# rgb.net
KiCad netlist of a schematic drawn in EAGLE
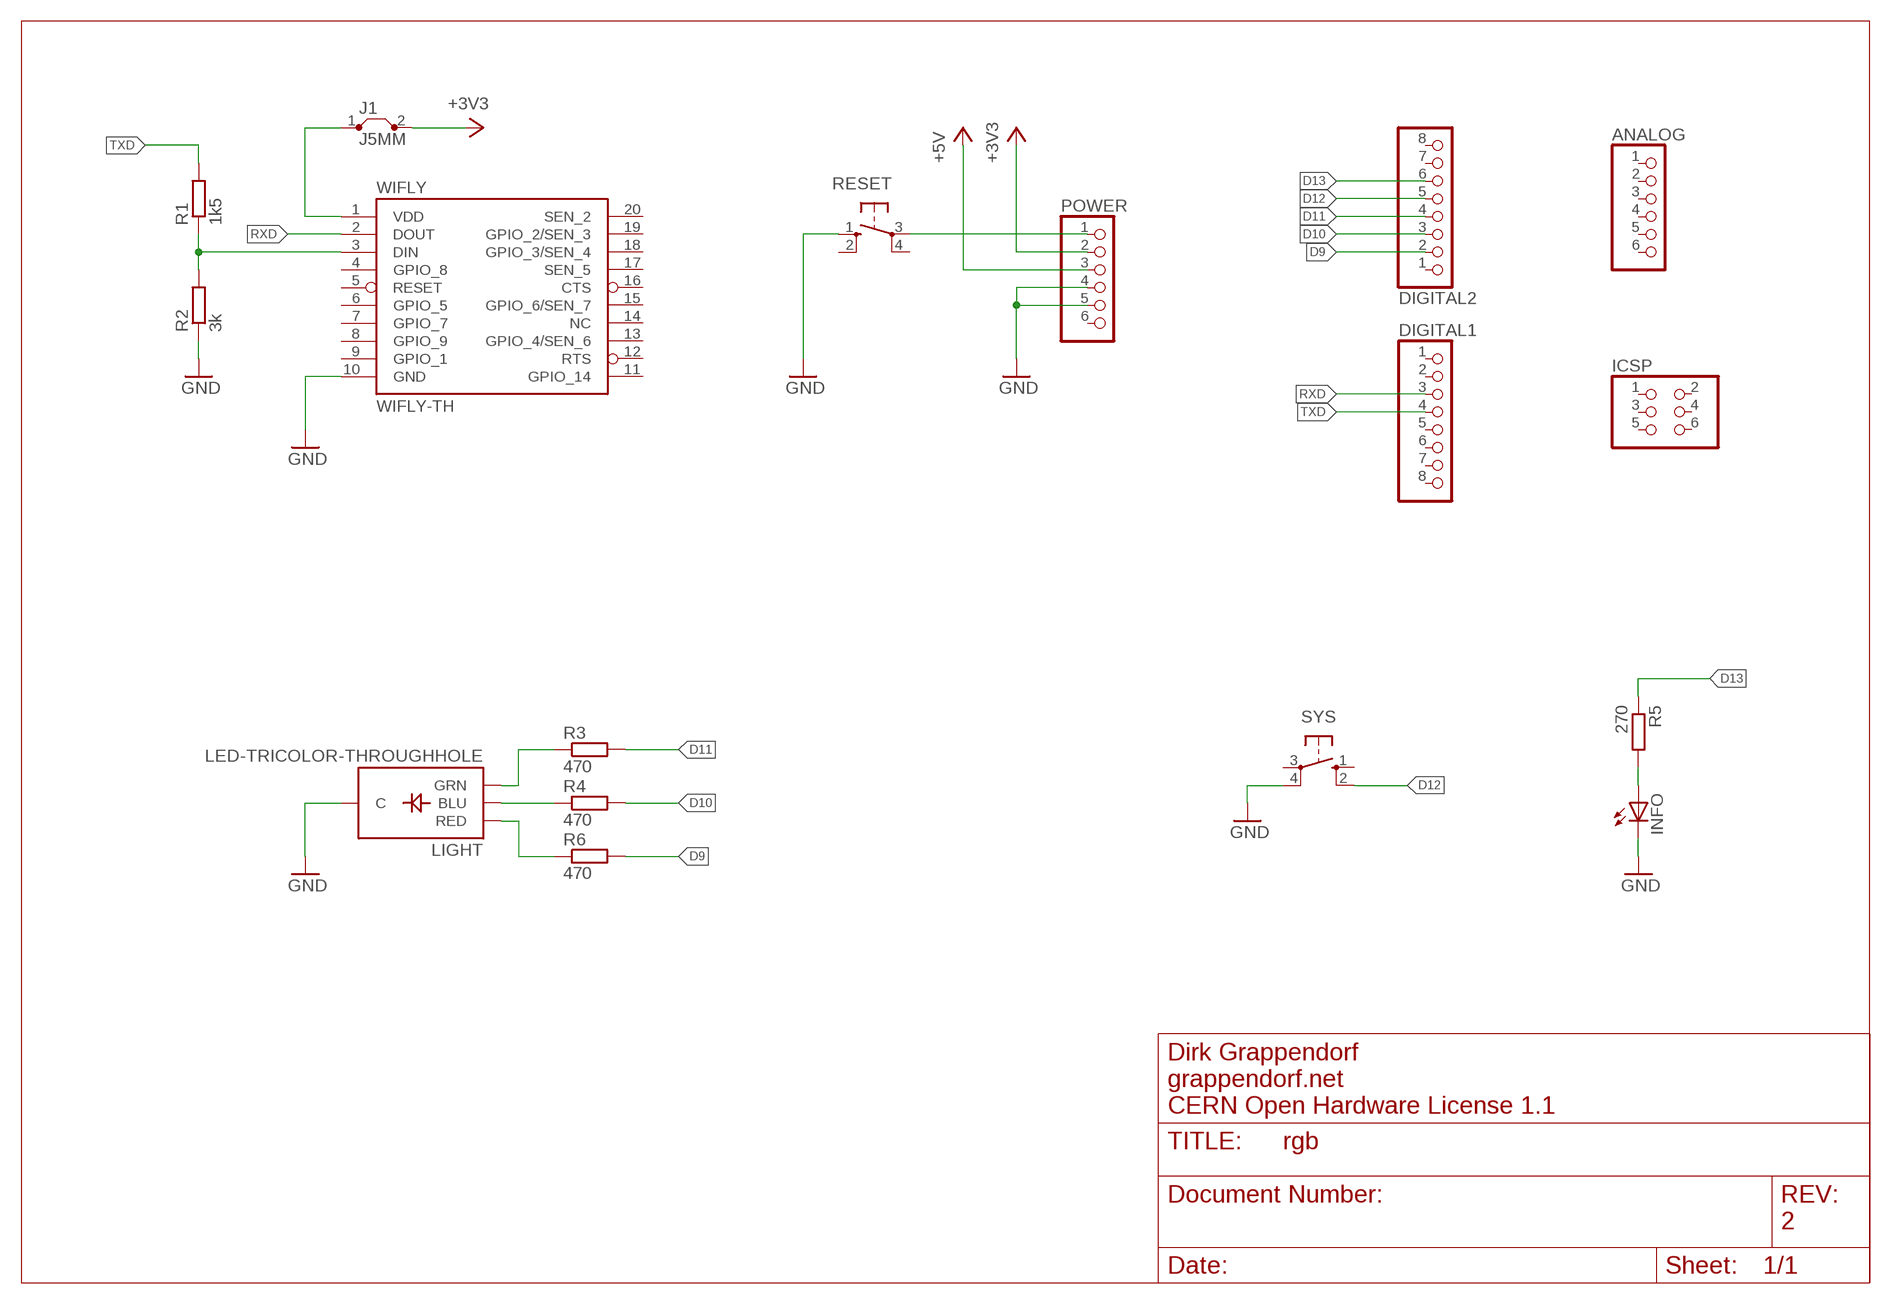
[diagram p0: schematic, sheet 1]

(export (version "E")
  (design (tool "Eeschema 10.0.6"))
  (components
    (comp (ref "ANALOG")
      (value "PINHD-1X6")
      (footprint "eagle-import:1X06")
      (libsource (lib "eagle-import") (part "PINHD-1X6"))
    )
    (comp (ref "DIGITAL1")
      (value "PINHD-1X8TH")
      (footprint "eagle-import:1X08-TH")
      (libsource (lib "eagle-import") (part "PINHD-1X8TH"))
    )
    (comp (ref "DIGITAL2")
      (value "PINHD-1X8_2.54")
      (footprint "eagle-import:1X08")
      (libsource (lib "eagle-import") (part "PINHD-1X8_2.54"))
    )
    (comp (ref "ICSP")
      (value "PINHD-2X3")
      (footprint "eagle-import:2X03")
      (libsource (lib "eagle-import") (part "PINHD-2X3"))
    )
    (comp (ref "INFO")
      (value "LED3MM")
      (footprint "eagle-import:LED3MM")
      (libsource (lib "eagle-import") (part "LED3MM"))
    )
    (comp (ref "J1")
      (value "J5MM")
      (footprint "eagle-import:05")
      (libsource (lib "eagle-import") (part "J5MM"))
    )
    (comp (ref "LIGHT")
      (value "LED-TRICOLOR-THROUGHHOLE")
      (footprint "eagle-import:LED-TRICOLOR-THROUGHHOLE")
      (libsource (lib "eagle-import") (part "LED-TRICOLOR-THROUGHHOLE"))
    )
    (comp (ref "POWER")
      (value "PINHD-1X6_2.54")
      (footprint "eagle-import:1X06")
      (libsource (lib "eagle-import") (part "PINHD-1X6_2.54"))
    )
    (comp (ref "R1")
      (value "1k5")
      (footprint "eagle-import:0204_7")
      (libsource (lib "eagle-import") (part "R-EU_0204/7"))
    )
    (comp (ref "R2")
      (value "3k")
      (footprint "eagle-import:0204_7")
      (libsource (lib "eagle-import") (part "R-EU_0204/7"))
    )
    (comp (ref "R3")
      (value "470")
      (footprint "eagle-import:0204_7")
      (libsource (lib "eagle-import") (part "R-EU_0204/7"))
    )
    (comp (ref "R4")
      (value "470")
      (footprint "eagle-import:0204_7")
      (libsource (lib "eagle-import") (part "R-EU_0204/7"))
    )
    (comp (ref "R5")
      (value "270")
      (footprint "eagle-import:0204_7")
      (libsource (lib "eagle-import") (part "R-EU_0204/7"))
    )
    (comp (ref "R6")
      (value "470")
      (footprint "eagle-import:0204_7")
      (libsource (lib "eagle-import") (part "R-EU_0204/7"))
    )
    (comp (ref "RESET")
      (value "10-XX")
      (footprint "eagle-import:B3F-10XX")
      (libsource (lib "eagle-import") (part "10-XX"))
    )
    (comp (ref "SYS")
      (value "10-XX")
      (footprint "eagle-import:B3F-10XX")
      (libsource (lib "eagle-import") (part "10-XX"))
    )
    (comp (ref "WIFLY")
      (value "WIFLY-TH")
      (footprint "eagle-import:WIFLY-TH")
      (libsource (lib "eagle-import") (part "WIFLY-TH"))
    )
  )
  (nets
    (net (code "1") (name "+3V3") (class "Default")
      (node (ref "J1") (pin "2") (pinfunction "2_2") (pintype "passive"))
      (node (ref "POWER") (pin "2") (pinfunction "2_2") (pintype "passive"))
    )
    (net (code "2") (name "+5V") (class "Default")
      (node (ref "POWER") (pin "3") (pinfunction "3_3") (pintype "passive"))
    )
    (net (code "3") (name "D9") (class "Default")
      (node (ref "DIGITAL2") (pin "2") (pinfunction "2_2") (pintype "passive"))
      (node (ref "R6") (pin "2") (pinfunction "2_2") (pintype "passive"))
    )
    (net (code "4") (name "D10") (class "Default")
      (node (ref "DIGITAL2") (pin "3") (pinfunction "3_3") (pintype "passive"))
      (node (ref "R4") (pin "2") (pinfunction "2_2") (pintype "passive"))
    )
    (net (code "5") (name "D11") (class "Default")
      (node (ref "DIGITAL2") (pin "4") (pinfunction "4_4") (pintype "passive"))
      (node (ref "R3") (pin "2") (pinfunction "2_2") (pintype "passive"))
    )
    (net (code "6") (name "D12") (class "Default")
      (node (ref "DIGITAL2") (pin "5") (pinfunction "5_5") (pintype "passive"))
      (node (ref "SYS") (pin "2") (pinfunction "S1_2") (pintype "passive"))
    )
    (net (code "7") (name "D13") (class "Default")
      (node (ref "DIGITAL2") (pin "6") (pinfunction "6_6") (pintype "passive"))
      (node (ref "R5") (pin "1") (pinfunction "1_1") (pintype "passive"))
    )
    (net (code "8") (name "GND") (class "Default")
      (node (ref "INFO") (pin "K") (pinfunction "C_K") (pintype "passive"))
      (node (ref "LIGHT") (pin "GND") (pinfunction "C_GND") (pintype "bidirectional"))
      (node (ref "POWER") (pin "4") (pinfunction "4_4") (pintype "passive"))
      (node (ref "POWER") (pin "5") (pinfunction "5_5") (pintype "passive"))
      (node (ref "R2") (pin "1") (pinfunction "1_1") (pintype "passive"))
      (node (ref "RESET") (pin "1") (pinfunction "S_1") (pintype "passive"))
      (node (ref "SYS") (pin "4") (pinfunction "P1_4") (pintype "passive"))
      (node (ref "WIFLY") (pin "10") (pinfunction "GND_10") (pintype "power_in"))
    )
    (net (code "9") (name "Net-(INFO-PadA)") (class "Default")
      (node (ref "INFO") (pin "A") (pinfunction "A_A") (pintype "passive"))
      (node (ref "R5") (pin "2") (pinfunction "2_2") (pintype "passive"))
    )
    (net (code "10") (name "Net-(LIGHT-PadBLU)") (class "Default")
      (node (ref "LIGHT") (pin "BLU") (pinfunction "BLU_BLU") (pintype "bidirectional"))
      (node (ref "R4") (pin "1") (pinfunction "1_1") (pintype "passive"))
    )
    (net (code "11") (name "Net-(LIGHT-PadGRN)") (class "Default")
      (node (ref "LIGHT") (pin "GRN") (pinfunction "GRN_GRN") (pintype "bidirectional"))
      (node (ref "R3") (pin "1") (pinfunction "1_1") (pintype "passive"))
    )
    (net (code "12") (name "Net-(LIGHT-PadRED)") (class "Default")
      (node (ref "LIGHT") (pin "RED") (pinfunction "RED_RED") (pintype "bidirectional"))
      (node (ref "R6") (pin "1") (pinfunction "1_1") (pintype "passive"))
    )
    (net (code "13") (name "Net-(RESET-P)") (class "Default")
      (node (ref "POWER") (pin "1") (pinfunction "1_1") (pintype "passive"))
      (node (ref "RESET") (pin "3") (pinfunction "P_3") (pintype "passive"))
    )
    (net (code "14") (name "Net-(WIFLY-DIN)") (class "Default")
      (node (ref "R1") (pin "1") (pinfunction "1_1") (pintype "passive"))
      (node (ref "R2") (pin "2") (pinfunction "2_2") (pintype "passive"))
      (node (ref "WIFLY") (pin "3") (pinfunction "DIN_3") (pintype "input"))
    )
    (net (code "15") (name "Net-(WIFLY-VDD)") (class "Default")
      (node (ref "J1") (pin "1") (pinfunction "1_1") (pintype "passive"))
      (node (ref "WIFLY") (pin "1") (pinfunction "VDD_1") (pintype "power_in"))
    )
    (net (code "16") (name "RXD") (class "Default")
      (node (ref "DIGITAL1") (pin "3") (pinfunction "3_3") (pintype "passive"))
      (node (ref "WIFLY") (pin "2") (pinfunction "DOUT_2") (pintype "output"))
    )
    (net (code "17") (name "TXD") (class "Default")
      (node (ref "DIGITAL1") (pin "4") (pinfunction "4_4") (pintype "passive"))
      (node (ref "R1") (pin "2") (pinfunction "2_2") (pintype "passive"))
    )
    (net (code "18") (name "unconnected-(ANALOG-Pad1)") (class "Default")
      (node (ref "ANALOG") (pin "1") (pinfunction "1_1") (pintype "passive"))
    )
    (net (code "19") (name "unconnected-(ANALOG-Pad2)") (class "Default")
      (node (ref "ANALOG") (pin "2") (pinfunction "2_2") (pintype "passive"))
    )
    (net (code "20") (name "unconnected-(ANALOG-Pad3)") (class "Default")
      (node (ref "ANALOG") (pin "3") (pinfunction "3_3") (pintype "passive"))
    )
    (net (code "21") (name "unconnected-(ANALOG-Pad4)") (class "Default")
      (node (ref "ANALOG") (pin "4") (pinfunction "4_4") (pintype "passive"))
    )
    (net (code "22") (name "unconnected-(ANALOG-Pad5)") (class "Default")
      (node (ref "ANALOG") (pin "5") (pinfunction "5_5") (pintype "passive"))
    )
    (net (code "23") (name "unconnected-(ANALOG-Pad6)") (class "Default")
      (node (ref "ANALOG") (pin "6") (pinfunction "6_6") (pintype "passive"))
    )
    (net (code "24") (name "unconnected-(DIGITAL1-Pad1)") (class "Default")
      (node (ref "DIGITAL1") (pin "1") (pinfunction "1_1") (pintype "passive"))
    )
    (net (code "25") (name "unconnected-(DIGITAL1-Pad2)") (class "Default")
      (node (ref "DIGITAL1") (pin "2") (pinfunction "2_2") (pintype "passive"))
    )
    (net (code "26") (name "unconnected-(DIGITAL1-Pad5)") (class "Default")
      (node (ref "DIGITAL1") (pin "5") (pinfunction "5_5") (pintype "passive"))
    )
    (net (code "27") (name "unconnected-(DIGITAL1-Pad6)") (class "Default")
      (node (ref "DIGITAL1") (pin "6") (pinfunction "6_6") (pintype "passive"))
    )
    (net (code "28") (name "unconnected-(DIGITAL1-Pad7)") (class "Default")
      (node (ref "DIGITAL1") (pin "7") (pinfunction "7_7") (pintype "passive"))
    )
    (net (code "29") (name "unconnected-(DIGITAL1-Pad8)") (class "Default")
      (node (ref "DIGITAL1") (pin "8") (pinfunction "8_8") (pintype "passive"))
    )
    (net (code "30") (name "unconnected-(DIGITAL2-Pad1)") (class "Default")
      (node (ref "DIGITAL2") (pin "1") (pinfunction "1_1") (pintype "passive"))
    )
    (net (code "31") (name "unconnected-(DIGITAL2-Pad7)") (class "Default")
      (node (ref "DIGITAL2") (pin "7") (pinfunction "7_7") (pintype "passive"))
    )
    (net (code "32") (name "unconnected-(DIGITAL2-Pad8)") (class "Default")
      (node (ref "DIGITAL2") (pin "8") (pinfunction "8_8") (pintype "passive"))
    )
    (net (code "33") (name "unconnected-(ICSP-Pad1)") (class "Default")
      (node (ref "ICSP") (pin "1") (pinfunction "1_1") (pintype "passive"))
    )
    (net (code "34") (name "unconnected-(ICSP-Pad2)") (class "Default")
      (node (ref "ICSP") (pin "2") (pinfunction "2_2") (pintype "passive"))
    )
    (net (code "35") (name "unconnected-(ICSP-Pad3)") (class "Default")
      (node (ref "ICSP") (pin "3") (pinfunction "3_3") (pintype "passive"))
    )
    (net (code "36") (name "unconnected-(ICSP-Pad4)") (class "Default")
      (node (ref "ICSP") (pin "4") (pinfunction "4_4") (pintype "passive"))
    )
    (net (code "37") (name "unconnected-(ICSP-Pad5)") (class "Default")
      (node (ref "ICSP") (pin "5") (pinfunction "5_5") (pintype "passive"))
    )
    (net (code "38") (name "unconnected-(ICSP-Pad6)") (class "Default")
      (node (ref "ICSP") (pin "6") (pinfunction "6_6") (pintype "passive"))
    )
    (net (code "39") (name "unconnected-(POWER-Pad6)") (class "Default")
      (node (ref "POWER") (pin "6") (pinfunction "6_6") (pintype "passive"))
    )
    (net (code "40") (name "unconnected-(RESET-P1-Pad4)") (class "Default")
      (node (ref "RESET") (pin "4") (pinfunction "P1_4") (pintype "passive"))
    )
    (net (code "41") (name "unconnected-(RESET-S1-Pad2)") (class "Default")
      (node (ref "RESET") (pin "2") (pinfunction "S1_2") (pintype "passive"))
    )
    (net (code "42") (name "unconnected-(SYS-P-Pad3)") (class "Default")
      (node (ref "SYS") (pin "3") (pinfunction "P_3") (pintype "passive"))
    )
    (net (code "43") (name "unconnected-(SYS-S-Pad1)") (class "Default")
      (node (ref "SYS") (pin "1") (pinfunction "S_1") (pintype "passive"))
    )
    (net (code "44") (name "unconnected-(WIFLY-CTS-Pad16)") (class "Default")
      (node (ref "WIFLY") (pin "16") (pinfunction "CTS_16") (pintype "input"))
    )
    (net (code "45") (name "unconnected-(WIFLY-GPIO_1-Pad9)") (class "Default")
      (node (ref "WIFLY") (pin "9") (pinfunction "GPIO_1_9") (pintype "bidirectional"))
    )
    (net (code "46") (name "unconnected-(WIFLY-GPIO_2{slash}SEN_3-Pad19)") (class "Default")
      (node (ref "WIFLY") (pin "19") (pinfunction "GPIO_2/SEN_3_19") (pintype "bidirectional"))
    )
    (net (code "47") (name "unconnected-(WIFLY-GPIO_3{slash}SEN_4-Pad18)") (class "Default")
      (node (ref "WIFLY") (pin "18") (pinfunction "GPIO_3/SEN_4_18") (pintype "bidirectional"))
    )
    (net (code "48") (name "unconnected-(WIFLY-GPIO_4{slash}SEN_6-Pad13)") (class "Default")
      (node (ref "WIFLY") (pin "13") (pinfunction "GPIO_4/SEN_6_13") (pintype "bidirectional"))
    )
    (net (code "49") (name "unconnected-(WIFLY-GPIO_5-Pad6)") (class "Default")
      (node (ref "WIFLY") (pin "6") (pinfunction "GPIO_5_6") (pintype "bidirectional"))
    )
    (net (code "50") (name "unconnected-(WIFLY-GPIO_6{slash}SEN_7-Pad15)") (class "Default")
      (node (ref "WIFLY") (pin "15") (pinfunction "GPIO_6/SEN_7_15") (pintype "bidirectional"))
    )
    (net (code "51") (name "unconnected-(WIFLY-GPIO_7-Pad7)") (class "Default")
      (node (ref "WIFLY") (pin "7") (pinfunction "GPIO_7_7") (pintype "bidirectional"))
    )
    (net (code "52") (name "unconnected-(WIFLY-GPIO_8-Pad4)") (class "Default")
      (node (ref "WIFLY") (pin "4") (pinfunction "GPIO_8_4") (pintype "bidirectional"))
    )
    (net (code "53") (name "unconnected-(WIFLY-GPIO_9-Pad8)") (class "Default")
      (node (ref "WIFLY") (pin "8") (pinfunction "GPIO_9_8") (pintype "bidirectional"))
    )
    (net (code "54") (name "unconnected-(WIFLY-GPIO_14-Pad11)") (class "Default")
      (node (ref "WIFLY") (pin "11") (pinfunction "GPIO_14_11") (pintype "bidirectional"))
    )
    (net (code "55") (name "unconnected-(WIFLY-NC-Pad14)") (class "Default")
      (node (ref "WIFLY") (pin "14") (pinfunction "NC_14") (pintype "bidirectional"))
    )
    (net (code "56") (name "unconnected-(WIFLY-RESET-Pad5)") (class "Default")
      (node (ref "WIFLY") (pin "5") (pinfunction "RESET_5") (pintype "input"))
    )
    (net (code "57") (name "unconnected-(WIFLY-RTS-Pad12)") (class "Default")
      (node (ref "WIFLY") (pin "12") (pinfunction "RTS_12") (pintype "output"))
    )
    (net (code "58") (name "unconnected-(WIFLY-SEN_2-Pad20)") (class "Default")
      (node (ref "WIFLY") (pin "20") (pinfunction "SEN_2_20") (pintype "bidirectional"))
    )
    (net (code "59") (name "unconnected-(WIFLY-SEN_5-Pad17)") (class "Default")
      (node (ref "WIFLY") (pin "17") (pinfunction "SEN_5_17") (pintype "bidirectional"))
    )
  )
)
